# 2_-_Battery_Sensing.net
KiCad netlist of a schematic drawn in Altium Designer
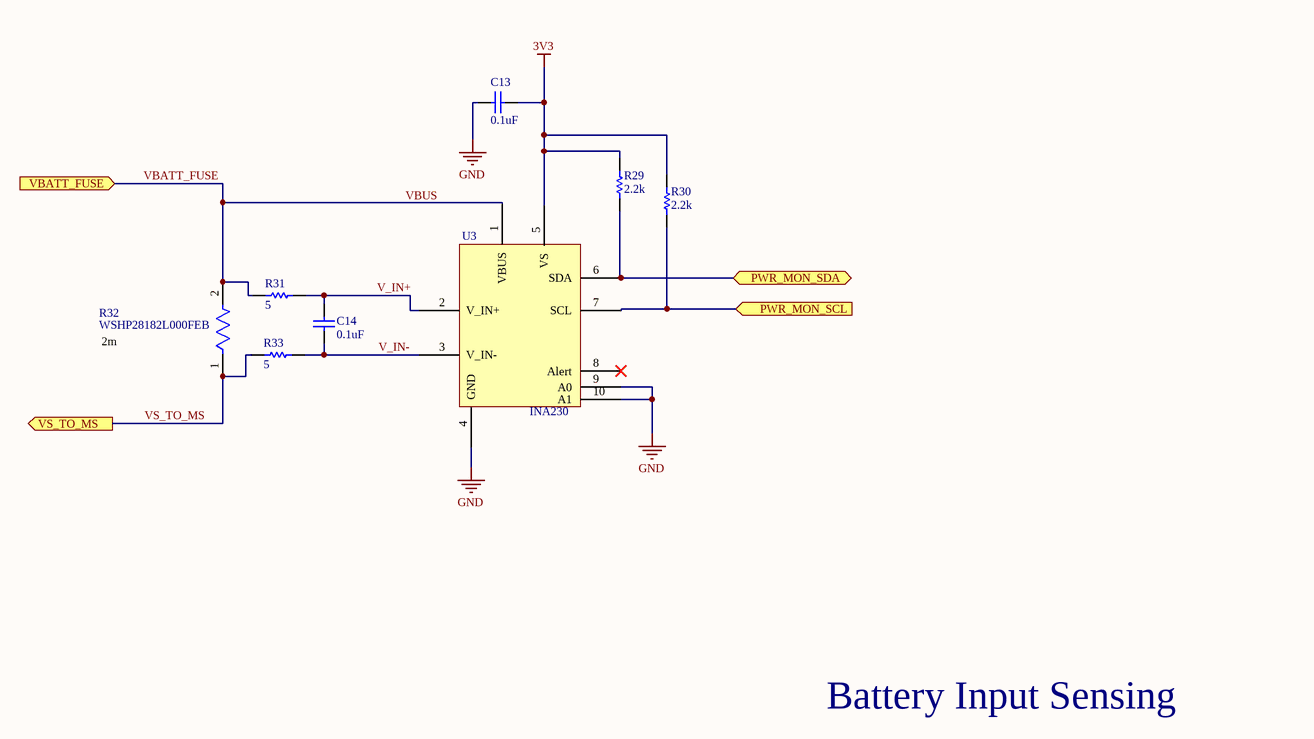
[diagram p0: 2  - Battery Sensing.SchDoc]

(export (version "E")
  (design (tool "Eeschema 10.0.6"))
  (components
    (comp (ref "C13")
      (value "0.1uF")
      (footprint "0603R-generic")
      (description "Capacitor")
      (fields
        (field (name "MANUFACTURER") "Yageo")
        (field (name "MANUFACTURER PART NUMBER") "CC1210ZKY5V8BB106")
      )
      (libsource (lib "Miscellaneous Devices") (part "Cap"))
    )
    (comp (ref "C14")
      (value "0.1uF")
      (footprint "0603R-generic")
      (description "Capacitor")
      (fields
        (field (name "MANUFACTURER") "Yageo")
        (field (name "MANUFACTURER PART NUMBER") "CC1210ZKY5V8BB106")
      )
      (libsource (lib "Miscellaneous Devices") (part "Cap"))
    )
    (comp (ref "R29")
      (value "2.2k")
      (footprint "RESC0603(1608)_L")
      (description "0603 (1608 Metric) Chip Resistor")
      (libsource (lib "Altium Content Vault") (part "RES_3"))
    )
    (comp (ref "R30")
      (value "2.2k")
      (footprint "RESC0603(1608)_L")
      (description "0603 (1608 Metric) Chip Resistor")
      (libsource (lib "Altium Content Vault") (part "RES_3"))
    )
    (comp (ref "R31")
      (value "5")
      (footprint "RESC0603(1608)_L")
      (description "0603 (1608 Metric) Chip Resistor")
      (libsource (lib "Altium Content Vault") (part "RES_3"))
    )
    (comp (ref "R32")
      (value "WSHP28182L000FEB")
      (footprint "FP-WSHP2818-MFG")
      (description "WSHP28182L000FEB Res Metal Strip 2818 0.002 Ohm 1% 10W ±200ppm/C Pad SMD Automotive T/R")
      (fields (field (name "TOLERANCE") "1%"))
      (libsource (lib "Altium Content Vault") (part "1029c3af85768c4190bb7ad29bc67b5"))
    )
    (comp (ref "R33")
      (value "5")
      (footprint "RESC0603(1608)_L")
      (description "0603 (1608 Metric) Chip Resistor")
      (libsource (lib "Altium Content Vault") (part "RES_3"))
    )
    (comp (ref "U3")
      (value "INA230")
      (footprint "SOP50P490X110-10N")
      (libsource (lib "ACB_lib") (part "INA230"))
    )
  )
  (nets
    (net (code "1") (name "/PWR_MON_SCL") (class "Default")
      (node (ref "R30") (pin "1") (pinfunction "1_1") (pintype "passive"))
      (node (ref "U3") (pin "7") (pinfunction "SCL_7") (pintype "passive"))
    )
    (net (code "2") (name "/PWR_MON_SDA") (class "Default")
      (node (ref "R29") (pin "1") (pinfunction "1_1") (pintype "passive"))
      (node (ref "U3") (pin "6") (pinfunction "SDA_6") (pintype "passive"))
    )
    (net (code "3") (name "/VBATT_FUSE") (class "Default")
      (node (ref "R31") (pin "2") (pinfunction "2_2") (pintype "passive"))
      (node (ref "R32") (pin "2") (pinfunction "2_2") (pintype "passive"))
      (node (ref "U3") (pin "1") (pinfunction "VBUS_1") (pintype "passive"))
    )
    (net (code "5") (name "/VS_TO_MS") (class "Default")
      (node (ref "R32") (pin "1") (pinfunction "1_1") (pintype "passive"))
      (node (ref "R33") (pin "2") (pinfunction "2_2") (pintype "passive"))
    )
    (net (code "6") (name "/V_IN+") (class "Default")
      (node (ref "C14") (pin "2") (pinfunction "2_2") (pintype "passive"))
      (node (ref "R31") (pin "1") (pinfunction "1_1") (pintype "passive"))
      (node (ref "U3") (pin "2") (pinfunction "V_IN+_2") (pintype "passive"))
    )
    (net (code "7") (name "/V_IN-") (class "Default")
      (node (ref "C14") (pin "1") (pinfunction "1_1") (pintype "passive"))
      (node (ref "R33") (pin "1") (pinfunction "1_1") (pintype "passive"))
      (node (ref "U3") (pin "3") (pinfunction "V_IN-_3") (pintype "passive"))
    )
    (net (code "8") (name "3V3") (class "Default")
      (node (ref "C13") (pin "1") (pinfunction "1_1") (pintype "passive"))
      (node (ref "R29") (pin "2") (pinfunction "2_2") (pintype "passive"))
      (node (ref "R30") (pin "2") (pinfunction "2_2") (pintype "passive"))
      (node (ref "U3") (pin "5") (pinfunction "VS_5") (pintype "passive"))
    )
    (net (code "9") (name "GND") (class "Default")
      (node (ref "C13") (pin "2") (pinfunction "2_2") (pintype "passive"))
      (node (ref "U3") (pin "10") (pinfunction "A1_10") (pintype "passive"))
      (node (ref "U3") (pin "4") (pinfunction "GND_4") (pintype "passive"))
      (node (ref "U3") (pin "9") (pinfunction "A0_9") (pintype "passive"))
    )
    (net (code "10") (name "unconnected-(U3-Alert-Pad8)") (class "Default")
      (node (ref "U3") (pin "8") (pinfunction "Alert_8") (pintype "passive+no_connect"))
    )
  )
)
